# SCH_espsomfyrts.net
KiCad netlist of a schematic drawn in EasyEDA
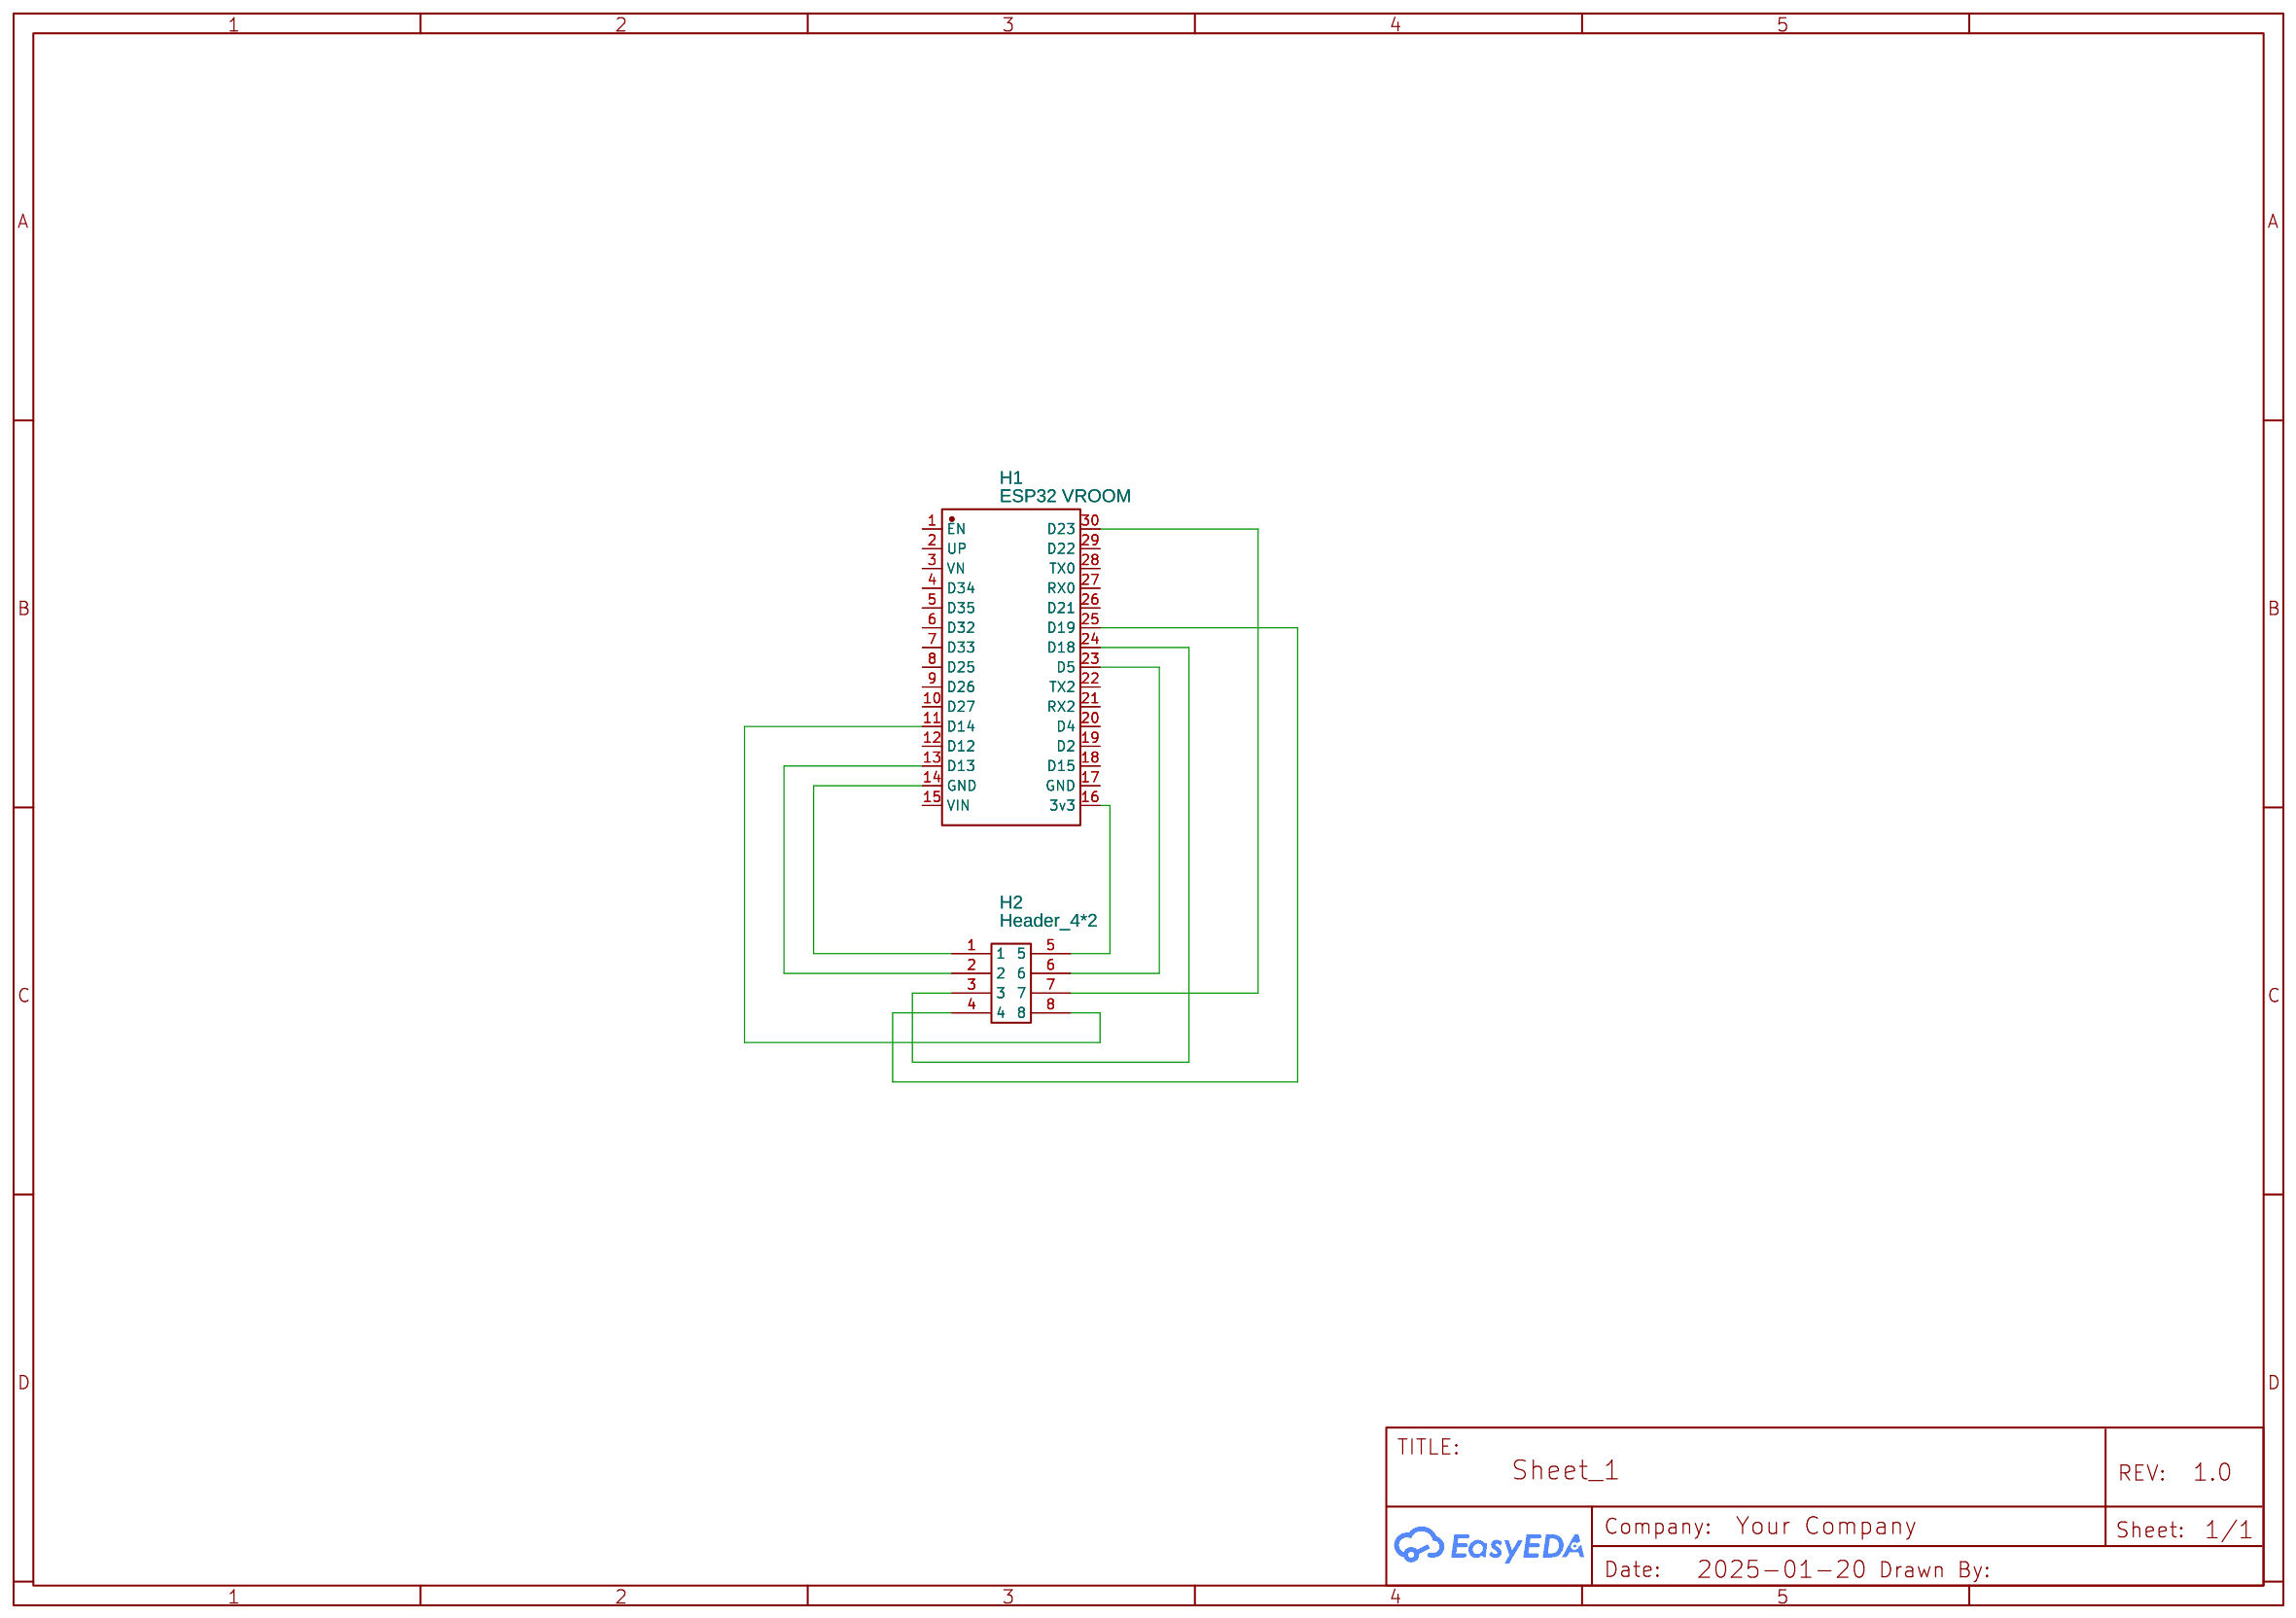
[diagram p0: schematic sheet]

(export (version "E")
  (design (tool "Eeschema 10.0.6"))
  (components
    (comp (ref "H1")
      (value "ESP32 VROOM")
      (fields (field (name "Manufacturer") "ReliaPro"))
      (libsource (lib "") (part "ESP32 VROOM"))
    )
    (comp (ref "H2") (value "Header_4*2") (libsource (lib "") (part "Header_4*2")))
  )
  (nets
    (net (code "1") (name "Net-(H1-3v3)") (class "Default")
      (node (ref "H1") (pin "16") (pinfunction "3v3_16") (pintype "unspecified"))
      (node (ref "H2") (pin "5") (pinfunction "5_5") (pintype "unspecified"))
    )
    (net (code "2") (name "Net-(H1-D5)") (class "Default")
      (node (ref "H1") (pin "23") (pinfunction "D5_23") (pintype "unspecified"))
      (node (ref "H2") (pin "6") (pinfunction "6_6") (pintype "unspecified"))
    )
    (net (code "3") (name "Net-(H1-D13)") (class "Default")
      (node (ref "H1") (pin "13") (pinfunction "D13_13") (pintype "unspecified"))
      (node (ref "H2") (pin "2") (pinfunction "2_2") (pintype "unspecified"))
    )
    (net (code "4") (name "Net-(H1-D14)") (class "Default")
      (node (ref "H1") (pin "11") (pinfunction "D14_11") (pintype "unspecified"))
      (node (ref "H2") (pin "8") (pinfunction "8_8") (pintype "unspecified"))
    )
    (net (code "5") (name "Net-(H1-D18)") (class "Default")
      (node (ref "H1") (pin "24") (pinfunction "D18_24") (pintype "unspecified"))
      (node (ref "H2") (pin "3") (pinfunction "3_3") (pintype "unspecified"))
    )
    (net (code "6") (name "Net-(H1-D19)") (class "Default")
      (node (ref "H1") (pin "25") (pinfunction "D19_25") (pintype "unspecified"))
      (node (ref "H2") (pin "4") (pinfunction "4_4") (pintype "unspecified"))
    )
    (net (code "7") (name "Net-(H1-D23)") (class "Default")
      (node (ref "H1") (pin "30") (pinfunction "D23_30") (pintype "unspecified"))
      (node (ref "H2") (pin "7") (pinfunction "7_7") (pintype "unspecified"))
    )
    (net (code "8") (name "Net-(H1-GND-Pad14)") (class "Default")
      (node (ref "H1") (pin "14") (pinfunction "GND_14") (pintype "unspecified"))
      (node (ref "H2") (pin "1") (pinfunction "1_1") (pintype "unspecified"))
    )
    (net (code "9") (name "unconnected-(H1-D2-Pad19)") (class "Default")
      (node (ref "H1") (pin "19") (pinfunction "D2_19") (pintype "unspecified"))
    )
    (net (code "10") (name "unconnected-(H1-D4-Pad20)") (class "Default")
      (node (ref "H1") (pin "20") (pinfunction "D4_20") (pintype "unspecified"))
    )
    (net (code "11") (name "unconnected-(H1-D12-Pad12)") (class "Default")
      (node (ref "H1") (pin "12") (pinfunction "D12_12") (pintype "unspecified"))
    )
    (net (code "12") (name "unconnected-(H1-D15-Pad18)") (class "Default")
      (node (ref "H1") (pin "18") (pinfunction "D15_18") (pintype "unspecified"))
    )
    (net (code "13") (name "unconnected-(H1-D21-Pad26)") (class "Default")
      (node (ref "H1") (pin "26") (pinfunction "D21_26") (pintype "unspecified"))
    )
    (net (code "14") (name "unconnected-(H1-D22-Pad29)") (class "Default")
      (node (ref "H1") (pin "29") (pinfunction "D22_29") (pintype "unspecified"))
    )
    (net (code "15") (name "unconnected-(H1-D25-Pad8)") (class "Default")
      (node (ref "H1") (pin "8") (pinfunction "D25_8") (pintype "unspecified"))
    )
    (net (code "16") (name "unconnected-(H1-D26-Pad9)") (class "Default")
      (node (ref "H1") (pin "9") (pinfunction "D26_9") (pintype "unspecified"))
    )
    (net (code "17") (name "unconnected-(H1-D27-Pad10)") (class "Default")
      (node (ref "H1") (pin "10") (pinfunction "D27_10") (pintype "unspecified"))
    )
    (net (code "18") (name "unconnected-(H1-D32-Pad6)") (class "Default")
      (node (ref "H1") (pin "6") (pinfunction "D32_6") (pintype "unspecified"))
    )
    (net (code "19") (name "unconnected-(H1-D33-Pad7)") (class "Default")
      (node (ref "H1") (pin "7") (pinfunction "D33_7") (pintype "unspecified"))
    )
    (net (code "20") (name "unconnected-(H1-D34-Pad4)") (class "Default")
      (node (ref "H1") (pin "4") (pinfunction "D34_4") (pintype "unspecified"))
    )
    (net (code "21") (name "unconnected-(H1-D35-Pad5)") (class "Default")
      (node (ref "H1") (pin "5") (pinfunction "D35_5") (pintype "unspecified"))
    )
    (net (code "22") (name "unconnected-(H1-EN-Pad1)") (class "Default")
      (node (ref "H1") (pin "1") (pinfunction "EN_1") (pintype "unspecified"))
    )
    (net (code "23") (name "unconnected-(H1-GND-Pad17)") (class "Default")
      (node (ref "H1") (pin "17") (pinfunction "GND_17") (pintype "unspecified"))
    )
    (net (code "24") (name "unconnected-(H1-RX0-Pad27)") (class "Default")
      (node (ref "H1") (pin "27") (pinfunction "RX0_27") (pintype "unspecified"))
    )
    (net (code "25") (name "unconnected-(H1-RX2-Pad21)") (class "Default")
      (node (ref "H1") (pin "21") (pinfunction "RX2_21") (pintype "unspecified"))
    )
    (net (code "26") (name "unconnected-(H1-TX0-Pad28)") (class "Default")
      (node (ref "H1") (pin "28") (pinfunction "TX0_28") (pintype "unspecified"))
    )
    (net (code "27") (name "unconnected-(H1-TX2-Pad22)") (class "Default")
      (node (ref "H1") (pin "22") (pinfunction "TX2_22") (pintype "unspecified"))
    )
    (net (code "28") (name "unconnected-(H1-UP-Pad2)") (class "Default")
      (node (ref "H1") (pin "2") (pinfunction "UP_2") (pintype "unspecified"))
    )
    (net (code "29") (name "unconnected-(H1-VIN-Pad15)") (class "Default")
      (node (ref "H1") (pin "15") (pinfunction "VIN_15") (pintype "unspecified"))
    )
    (net (code "30") (name "unconnected-(H1-VN-Pad3)") (class "Default")
      (node (ref "H1") (pin "3") (pinfunction "VN_3") (pintype "unspecified"))
    )
  )
)
